# SFP_PortA.net
KiCad netlist of a schematic drawn in Altium Designer
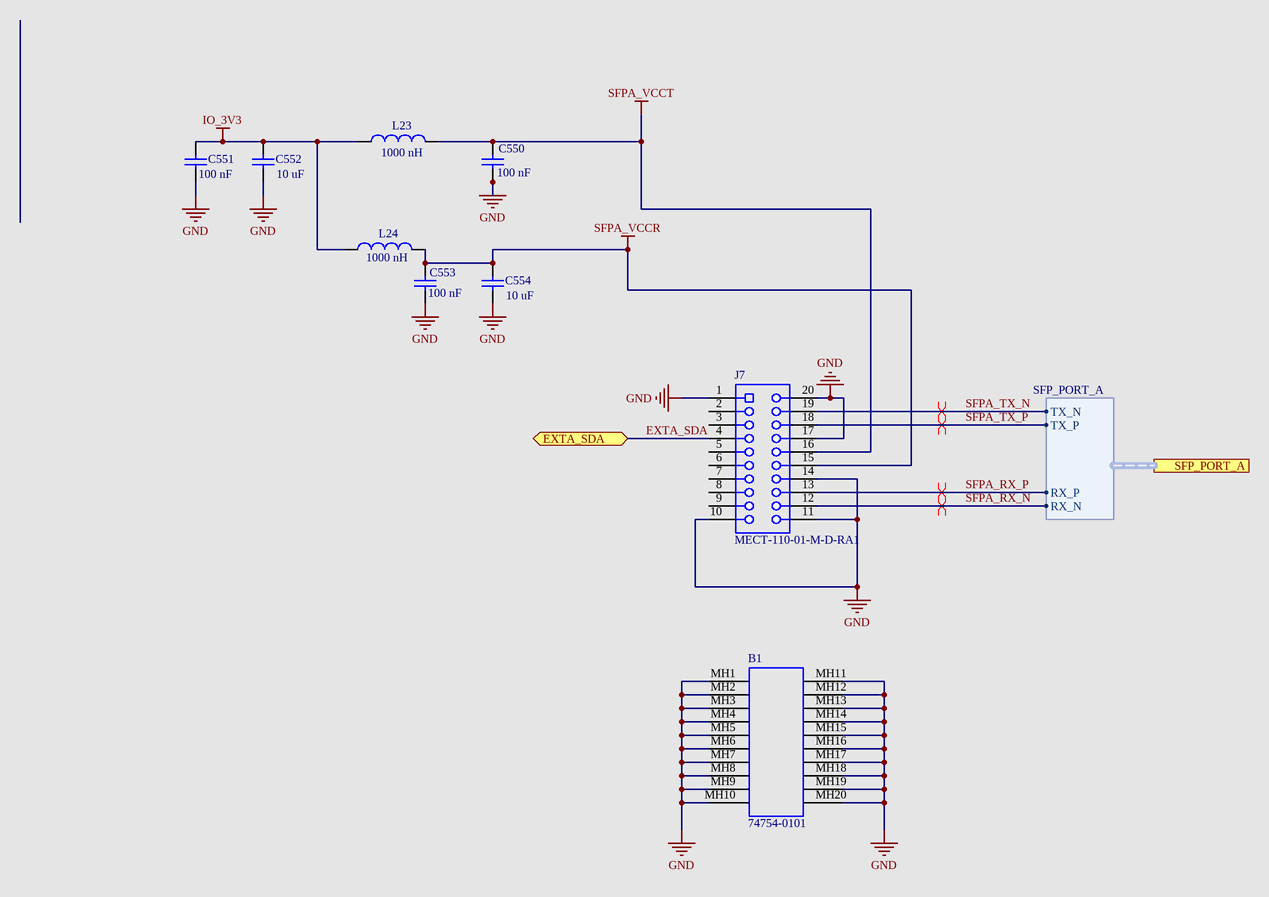
[diagram p0: SFP_PortA.SchDoc]

(export (version "E")
  (design (tool "Eeschema 10.0.6"))
  (components
    (comp (ref "B1")
      (value "74754-0101")
      (footprint "MOLX-74754-0101_V")
      (description "SFP+ Cage, Single Port, Height 10.85 mm, Tail Height 3.05 mm, -40 to 85 degC, RoHS, Tray")
      (fields (field (name "MANUFACTURER") "Molex"))
      (libsource (lib "Altium Content Vault") (part "MOLX-74754-0101"))
    )
    (comp (ref "C550")
      (value "C1005X7R1E104M")
      (footprint "CAPC1005X55X10LL05")
      (description "Chip Capacitor, 0.1 uF, +/- 20%, 25 V, -55 to 125 degC, 0402 (1005 Metric), RoHS, Tape and Reel")
      (fields (field (name "TOLERANCE") "20%") (field (name "CAPACITANCE") "100 nF"))
      (libsource (lib "Altium Content Vault") (part "CAP-NP-2"))
    )
    (comp (ref "C551")
      (value "C1005X7R1E104M")
      (footprint "CAPC1005X55X10LL05")
      (description "Chip Capacitor, 0.1 uF, +/- 20%, 25 V, -55 to 125 degC, 0402 (1005 Metric), RoHS, Tape and Reel")
      (fields (field (name "TOLERANCE") "20%") (field (name "CAPACITANCE") "100 nF"))
      (libsource (lib "Altium Content Vault") (part "CAP-NP-2"))
    )
    (comp (ref "C552")
      (value "C2012X5R1C106K085AC")
      (footprint "CAPC2013X100X20NL20")
      (description "Chip Capacitor, 10 uF, +/- 10%, 16 V, -55 to 85 degC, 0805 (2012 Metric), RoHS, Tape and Reel")
      (fields (field (name "TOLERANCE") "10%") (field (name "CAPACITANCE") "10 uF"))
      (libsource (lib "Altium Content Vault") (part "CMP-1663-00007-1"))
    )
    (comp (ref "C553")
      (value "C1005X7R1E104M")
      (footprint "CAPC1005X55X10LL05")
      (description "Chip Capacitor, 0.1 uF, +/- 20%, 25 V, -55 to 125 degC, 0402 (1005 Metric), RoHS, Tape and Reel")
      (fields (field (name "TOLERANCE") "20%") (field (name "CAPACITANCE") "100 nF"))
      (libsource (lib "Altium Content Vault") (part "CAP-NP-2"))
    )
    (comp (ref "C554")
      (value "C2012X5R1C106K085AC")
      (footprint "CAPC2013X100X20NL20")
      (description "Chip Capacitor, 10 uF, +/- 10%, 16 V, -55 to 85 degC, 0805 (2012 Metric), RoHS, Tape and Reel")
      (fields (field (name "TOLERANCE") "10%") (field (name "CAPACITANCE") "10 uF"))
      (libsource (lib "Altium Content Vault") (part "CMP-1663-00007-1"))
    )
    (comp (ref "J7")
      (value "MECT-110-01-M-D-RA1")
      (footprint "SMTC-MECT-110-01-M-D-RA1_V")
      (fields (field (name "MANUFACTURER") "Samtec"))
      (libsource (lib "Altium Content Vault") (part "CMP-1707-00001-1"))
    )
    (comp (ref "L23")
      (value "1008CS-102XFLC")
      (footprint "COIL-1008CS_V")
      (description "Chip Inductor, 1000 nH, +/- 1%, -40 to 125 degC, 2-Pin SMD, RoHS, Tape and Reel")
      (fields (field (name "INDUCTANCE") "1000 nH"))
      (libsource (lib "Altium Content Vault") (part "IND-2"))
    )
    (comp (ref "L24")
      (value "1008CS-102XFLC")
      (footprint "COIL-1008CS_V")
      (description "Chip Inductor, 1000 nH, +/- 1%, -40 to 125 degC, 2-Pin SMD, RoHS, Tape and Reel")
      (fields (field (name "INDUCTANCE") "1000 nH"))
      (libsource (lib "Altium Content Vault") (part "IND-2"))
    )
  )
  (nets
    (net (code "2") (name "/EXTA_SDA") (class "Default")
      (node (ref "J7") (pin "4") (pinfunction "4_4") (pintype "passive"))
    )
    (net (code "3") (name "/SFPA_RX_N") (class "Default")
      (node (ref "J7") (pin "12") (pinfunction "12_12") (pintype "passive"))
    )
    (net (code "4") (name "/SFPA_RX_P") (class "Default")
      (node (ref "J7") (pin "13") (pinfunction "13_13") (pintype "passive"))
    )
    (net (code "5") (name "/SFPA_TX_N") (class "Default")
      (node (ref "J7") (pin "19") (pinfunction "19_19") (pintype "passive"))
    )
    (net (code "6") (name "/SFPA_TX_P") (class "Default")
      (node (ref "J7") (pin "18") (pinfunction "18_18") (pintype "passive"))
    )
    (net (code "8") (name "GND") (class "Default")
      (node (ref "B1") (pin "MH1") (pinfunction "MH1_MH1") (pintype "passive"))
      (node (ref "B1") (pin "MH10") (pinfunction "MH10_MH10") (pintype "passive"))
      (node (ref "B1") (pin "MH11") (pinfunction "MH11_MH11") (pintype "passive"))
      (node (ref "B1") (pin "MH12") (pinfunction "MH12_MH12") (pintype "passive"))
      (node (ref "B1") (pin "MH13") (pinfunction "MH13_MH13") (pintype "passive"))
      (node (ref "B1") (pin "MH14") (pinfunction "MH14_MH14") (pintype "passive"))
      (node (ref "B1") (pin "MH15") (pinfunction "MH15_MH15") (pintype "passive"))
      (node (ref "B1") (pin "MH16") (pinfunction "MH16_MH16") (pintype "passive"))
      (node (ref "B1") (pin "MH17") (pinfunction "MH17_MH17") (pintype "passive"))
      (node (ref "B1") (pin "MH18") (pinfunction "MH18_MH18") (pintype "passive"))
      (node (ref "B1") (pin "MH19") (pinfunction "MH19_MH19") (pintype "passive"))
      (node (ref "B1") (pin "MH2") (pinfunction "MH2_MH2") (pintype "passive"))
      (node (ref "B1") (pin "MH20") (pinfunction "MH20_MH20") (pintype "passive"))
      (node (ref "B1") (pin "MH3") (pinfunction "MH3_MH3") (pintype "passive"))
      (node (ref "B1") (pin "MH4") (pinfunction "MH4_MH4") (pintype "passive"))
      (node (ref "B1") (pin "MH5") (pinfunction "MH5_MH5") (pintype "passive"))
      (node (ref "B1") (pin "MH6") (pinfunction "MH6_MH6") (pintype "passive"))
      (node (ref "B1") (pin "MH7") (pinfunction "MH7_MH7") (pintype "passive"))
      (node (ref "B1") (pin "MH8") (pinfunction "MH8_MH8") (pintype "passive"))
      (node (ref "B1") (pin "MH9") (pinfunction "MH9_MH9") (pintype "passive"))
      (node (ref "C550") (pin "1") (pinfunction "1_1") (pintype "passive"))
      (node (ref "C551") (pin "1") (pinfunction "1_1") (pintype "passive"))
      (node (ref "C552") (pin "1") (pinfunction "1_1") (pintype "passive"))
      (node (ref "C553") (pin "1") (pinfunction "1_1") (pintype "passive"))
      (node (ref "C554") (pin "1") (pinfunction "1_1") (pintype "passive"))
      (node (ref "J7") (pin "1") (pinfunction "1_1") (pintype "passive"))
      (node (ref "J7") (pin "10") (pinfunction "10_10") (pintype "passive"))
      (node (ref "J7") (pin "11") (pinfunction "11_11") (pintype "passive"))
      (node (ref "J7") (pin "14") (pinfunction "14_14") (pintype "passive"))
      (node (ref "J7") (pin "17") (pinfunction "17_17") (pintype "passive"))
      (node (ref "J7") (pin "20") (pinfunction "20_20") (pintype "passive"))
    )
    (net (code "9") (name "IO_3V3") (class "Default")
      (node (ref "C551") (pin "2") (pinfunction "2_2") (pintype "passive"))
      (node (ref "C552") (pin "2") (pinfunction "2_2") (pintype "passive"))
      (node (ref "L23") (pin "1") (pinfunction "1_1") (pintype "passive"))
      (node (ref "L24") (pin "1") (pinfunction "1_1") (pintype "passive"))
    )
    (net (code "10") (name "SFPA_VCCR") (class "Default")
      (node (ref "C553") (pin "2") (pinfunction "2_2") (pintype "passive"))
      (node (ref "C554") (pin "2") (pinfunction "2_2") (pintype "passive"))
      (node (ref "J7") (pin "15") (pinfunction "15_15") (pintype "passive"))
      (node (ref "L24") (pin "2") (pinfunction "2_2") (pintype "passive"))
    )
    (net (code "11") (name "SFPA_VCCT") (class "Default")
      (node (ref "C550") (pin "2") (pinfunction "2_2") (pintype "passive"))
      (node (ref "J7") (pin "16") (pinfunction "16_16") (pintype "passive"))
      (node (ref "L23") (pin "2") (pinfunction "2_2") (pintype "passive"))
    )
    (net (code "12") (name "unconnected-(J7-Pad2)") (class "Default")
      (node (ref "J7") (pin "2") (pinfunction "2_2") (pintype "passive"))
    )
    (net (code "13") (name "unconnected-(J7-Pad3)") (class "Default")
      (node (ref "J7") (pin "3") (pinfunction "3_3") (pintype "passive"))
    )
    (net (code "14") (name "unconnected-(J7-Pad5)") (class "Default")
      (node (ref "J7") (pin "5") (pinfunction "5_5") (pintype "passive"))
    )
    (net (code "15") (name "unconnected-(J7-Pad6)") (class "Default")
      (node (ref "J7") (pin "6") (pinfunction "6_6") (pintype "passive"))
    )
    (net (code "16") (name "unconnected-(J7-Pad7)") (class "Default")
      (node (ref "J7") (pin "7") (pinfunction "7_7") (pintype "passive"))
    )
    (net (code "17") (name "unconnected-(J7-Pad8)") (class "Default")
      (node (ref "J7") (pin "8") (pinfunction "8_8") (pintype "passive"))
    )
    (net (code "18") (name "unconnected-(J7-Pad9)") (class "Default")
      (node (ref "J7") (pin "9") (pinfunction "9_9") (pintype "passive"))
    )
  )
)
